# Control_HAT_v0_2A.net
KiCad netlist of a schematic drawn in EAGLE
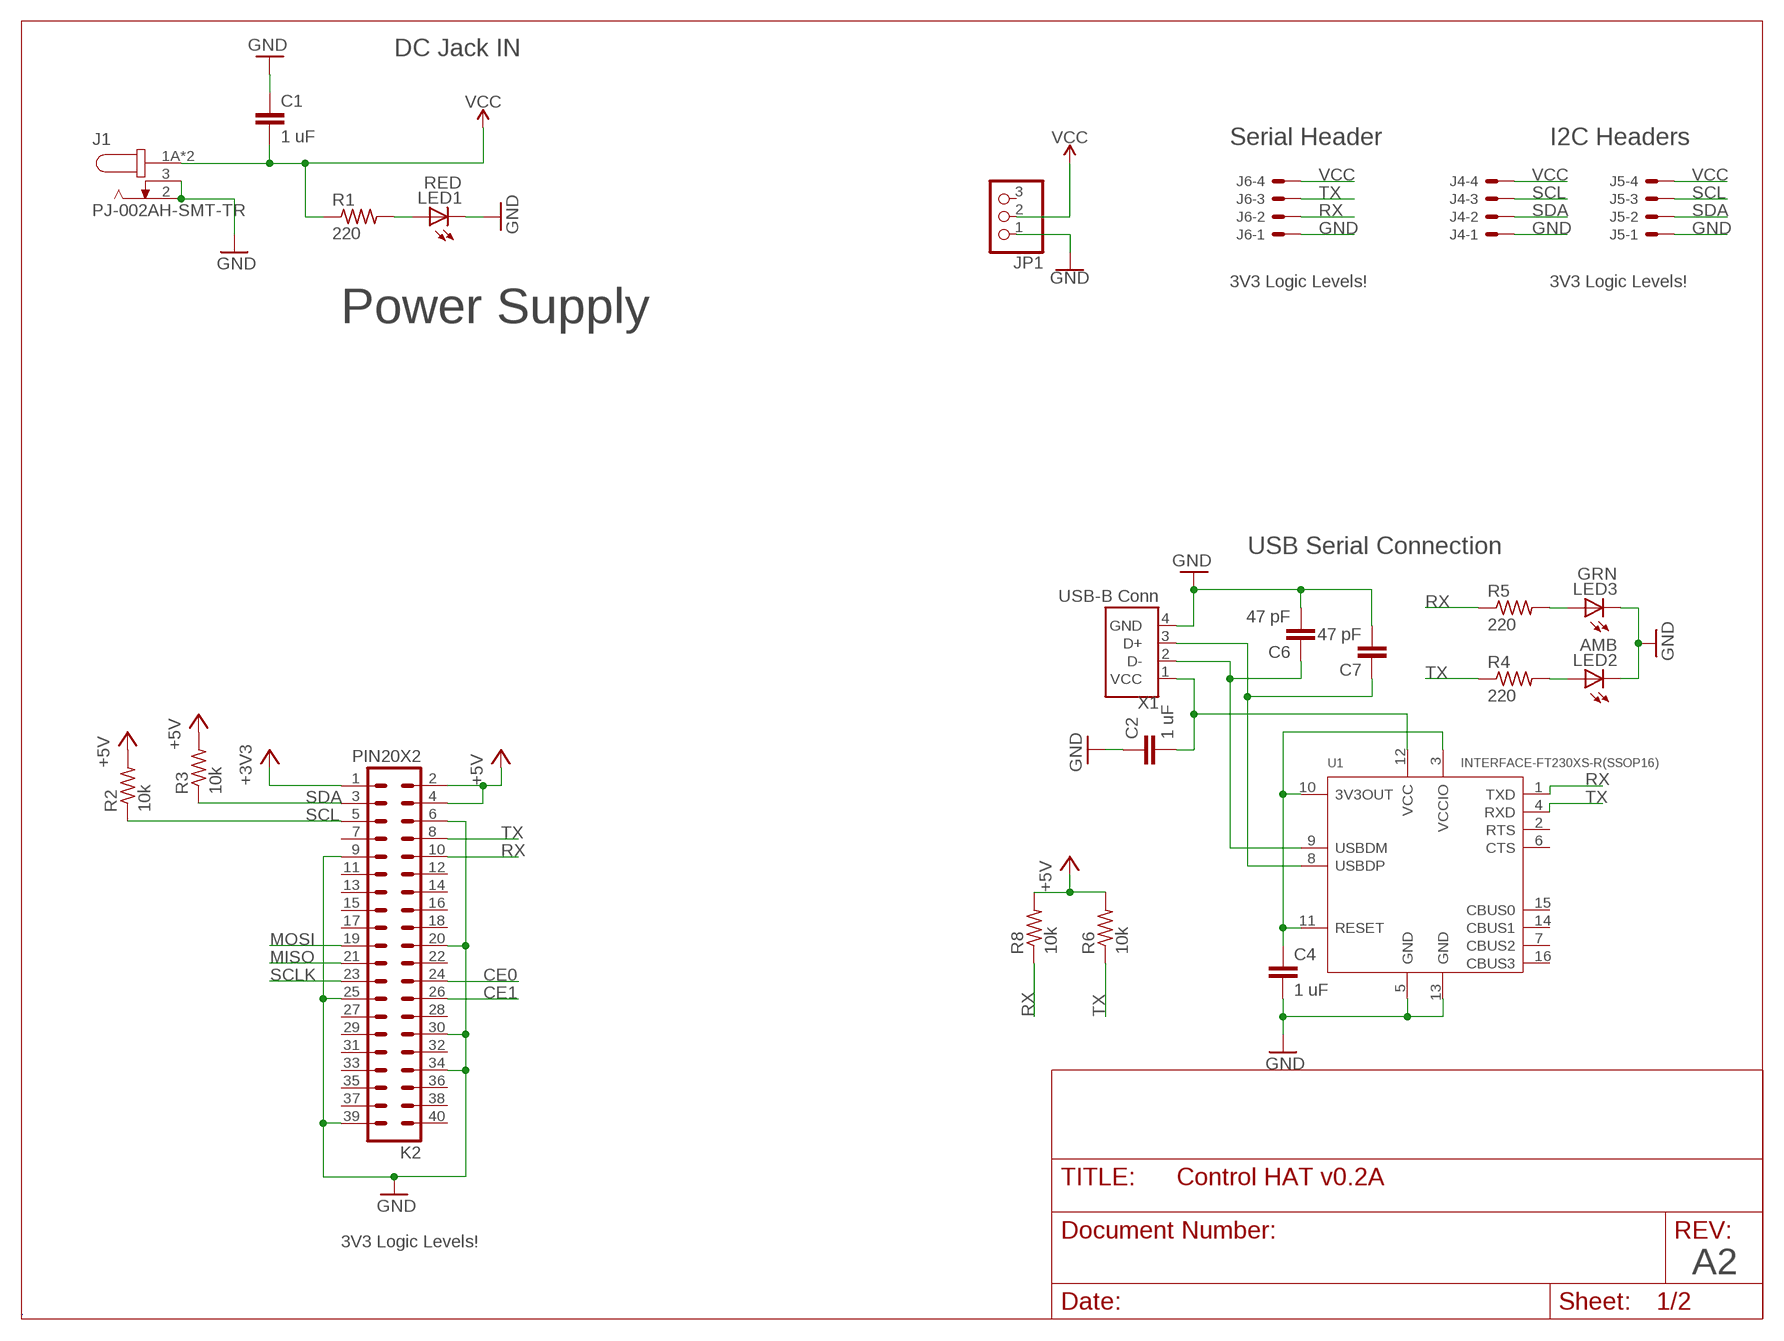
[diagram p0: schematic, sheet 1]
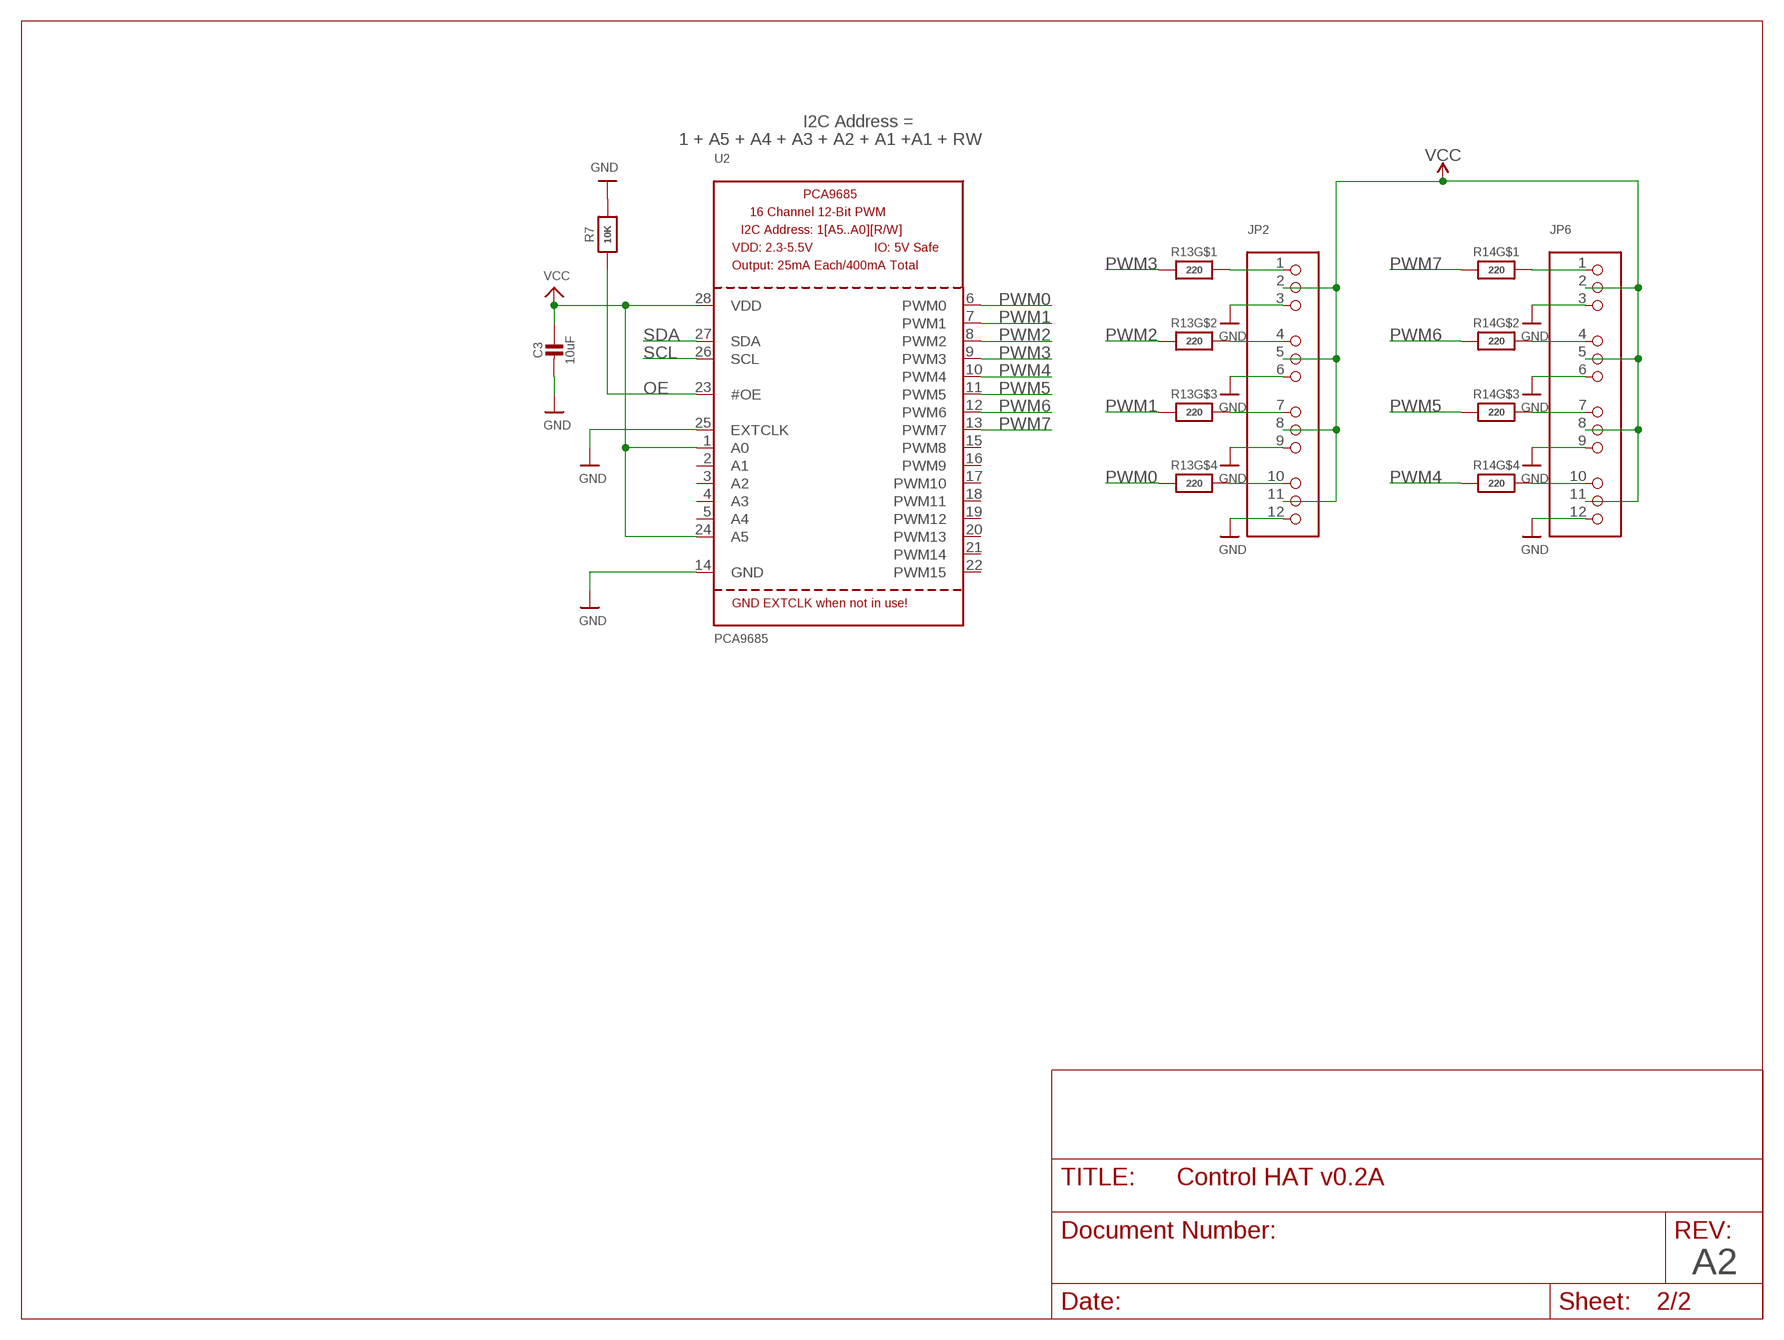
[diagram p1: schematic, sheet 2]

(export (version "E")
  (design (tool "Eeschema 10.0.6"))
  (components
    (comp (ref "C1")
      (value "1 uF")
      (footprint "eagle-import:C0603")
      (libsource (lib "eagle-import") (part "C-EUC0603"))
    )
    (comp (ref "C2")
      (value "1 uF")
      (footprint "eagle-import:C0603")
      (libsource (lib "eagle-import") (part "C-EUC0603"))
    )
    (comp (ref "C4")
      (value "1 uF")
      (footprint "eagle-import:C0603")
      (libsource (lib "eagle-import") (part "C-EUC0603"))
    )
    (comp (ref "C6")
      (value "47 pF")
      (footprint "eagle-import:C0603")
      (libsource (lib "eagle-import") (part "C-EUC0603"))
    )
    (comp (ref "C7")
      (value "47 pF")
      (footprint "eagle-import:C0603")
      (libsource (lib "eagle-import") (part "C-EUC0603"))
    )
    (comp (ref "J1")
      (value "PJ-002AH-SMT-TR")
      (footprint "eagle-import:CUI_PJ-002AH-SMT-TR")
      (fields (field (name "DIGI-KEY_PART_NUMBER") "CP-002AHPJCT-ND") (field (name "MF") "CUI Inc."))
      (libsource (lib "eagle-import") (part "PJ-002AH-SMT-TR"))
    )
    (comp (ref "J4")
      (value "JST-XH-04-PIN-LONG-PAD")
      (footprint "eagle-import:JST-XH-04-PACKAGE-LONG-PAD")
      (libsource (lib "eagle-import") (part "JST-XH-04-PIN-LONG-PAD"))
    )
    (comp (ref "J5")
      (value "JST-XH-04-PIN-LONG-PAD")
      (footprint "eagle-import:JST-XH-04-PACKAGE-LONG-PAD")
      (libsource (lib "eagle-import") (part "JST-XH-04-PIN-LONG-PAD"))
    )
    (comp (ref "J6")
      (value "JST-XH-04-PIN-LONG-PAD")
      (footprint "eagle-import:JST-XH-04-PACKAGE-LONG-PAD")
      (libsource (lib "eagle-import") (part "JST-XH-04-PIN-LONG-PAD"))
    )
    (comp (ref "JP1")
      (value "PINHD-1X3")
      (footprint "eagle-import:1X03")
      (libsource (lib "eagle-import") (part "PINHD-1X3"))
    )
    (comp (ref "K2")
      (value "PIN20X2")
      (footprint "eagle-import:PIN_20X2")
      (libsource (lib "eagle-import") (part "PIN20X2"))
    )
    (comp (ref "LED1")
      (value "RED")
      (footprint "eagle-import:CHIP-LED0603")
      (libsource (lib "eagle-import") (part "LEDCHIP-LED0603"))
    )
    (comp (ref "LED2")
      (value "AMB")
      (footprint "eagle-import:CHIP-LED0603")
      (libsource (lib "eagle-import") (part "LEDCHIP-LED0603"))
    )
    (comp (ref "LED3")
      (value "GRN")
      (footprint "eagle-import:CHIP-LED0603")
      (libsource (lib "eagle-import") (part "LEDCHIP-LED0603"))
    )
    (comp (ref "R1")
      (value "220")
      (footprint "eagle-import:M1206")
      (libsource (lib "eagle-import") (part "R-US_M1206"))
    )
    (comp (ref "R2")
      (value "10k")
      (footprint "eagle-import:M1206")
      (libsource (lib "eagle-import") (part "R-US_M1206"))
    )
    (comp (ref "R3")
      (value "10k")
      (footprint "eagle-import:M1206")
      (libsource (lib "eagle-import") (part "R-US_M1206"))
    )
    (comp (ref "R4")
      (value "220")
      (footprint "eagle-import:M1206")
      (libsource (lib "eagle-import") (part "R-US_M1206"))
    )
    (comp (ref "R5")
      (value "220")
      (footprint "eagle-import:M1206")
      (libsource (lib "eagle-import") (part "R-US_M1206"))
    )
    (comp (ref "R6")
      (value "10k")
      (footprint "eagle-import:M1206")
      (libsource (lib "eagle-import") (part "R-US_M1206"))
    )
    (comp (ref "R8")
      (value "10k")
      (footprint "eagle-import:M1206")
      (libsource (lib "eagle-import") (part "R-US_M1206"))
    )
    (comp (ref "U1")
      (value "INTERFACE-FT230XS-R(SSOP16)")
      (footprint "eagle-import:SSOP16-0.635-5X4MM")
      (fields (field (name "MF") "FTDI,") (field (name "MP") "FT230XS-R"))
      (libsource (lib "eagle-import") (part "INTERFACE-FT230XS-R(SSOP16)"))
    )
    (comp (ref "X1")
      (value "USB-B Conn")
      (footprint "eagle-import:OST_USB-B1HSB6")
      (fields (field (name "MF") "On Shore") (field (name "MP") "USB-B1HSB6"))
      (libsource (lib "eagle-import") (part "USB-B1HSB6"))
    )
    (comp (ref "C3")
      (value "10uF")
      (footprint "eagle-import:0805-NO")
      (libsource (lib "eagle-import") (part "CAP_CERAMIC0805-NOOUTLINE"))
    )
    (comp (ref "JP2")
      (value "HEADER-3X04")
      (footprint "eagle-import:3X04")
      (libsource (lib "eagle-import") (part "HEADER-3X04"))
    )
    (comp (ref "JP6")
      (value "HEADER-3X04")
      (footprint "eagle-import:3X04")
      (libsource (lib "eagle-import") (part "HEADER-3X04"))
    )
    (comp (ref "R7")
      (value "10K")
      (footprint "eagle-import:0805-NO")
      (libsource (lib "eagle-import") (part "RESISTOR0805_NOOUTLINE"))
    )
    (comp (ref "R13")
      (value "220")
      (footprint "eagle-import:RESPACK_4X0603")
      (libsource (lib "eagle-import") (part "RESISTOR_4PACK"))
    )
    (comp (ref "R14")
      (value "220")
      (footprint "eagle-import:RESPACK_4X0603")
      (libsource (lib "eagle-import") (part "RESISTOR_4PACK"))
    )
    (comp (ref "U2")
      (value "PCA9685")
      (footprint "eagle-import:TSSOP28")
      (libsource (lib "eagle-import") (part "PCA9685"))
    )
  )
  (nets
    (net (code "1") (name "+3V3") (class "Default")
      (node (ref "K2") (pin "1") (pinfunction "1_1") (pintype "passive"))
    )
    (net (code "2") (name "+5V") (class "Default")
      (node (ref "K2") (pin "2") (pinfunction "2_2") (pintype "passive"))
      (node (ref "K2") (pin "4") (pinfunction "4_4") (pintype "passive"))
      (node (ref "R2") (pin "2") (pinfunction "2_2") (pintype "passive"))
      (node (ref "R3") (pin "2") (pinfunction "2_2") (pintype "passive"))
      (node (ref "R6") (pin "2") (pinfunction "2_2") (pintype "passive"))
      (node (ref "R8") (pin "2") (pinfunction "2_2") (pintype "passive"))
    )
    (net (code "3") (name "CE0") (class "Default")
      (node (ref "K2") (pin "24") (pinfunction "24_24") (pintype "passive"))
    )
    (net (code "4") (name "CE1") (class "Default")
      (node (ref "K2") (pin "26") (pinfunction "26_26") (pintype "passive"))
    )
    (net (code "5") (name "GND") (class "Default")
      (node (ref "C1") (pin "1") (pinfunction "1_1") (pintype "passive"))
      (node (ref "C2") (pin "1") (pinfunction "1_1") (pintype "passive"))
      (node (ref "C3") (pin "2") (pinfunction "2_2") (pintype "passive"))
      (node (ref "C4") (pin "2") (pinfunction "2_2") (pintype "passive"))
      (node (ref "C6") (pin "2") (pinfunction "2_2") (pintype "passive"))
      (node (ref "C7") (pin "2") (pinfunction "2_2") (pintype "passive"))
      (node (ref "J1") (pin "2") (pinfunction "2_2") (pintype "passive"))
      (node (ref "J1") (pin "3") (pinfunction "3_3") (pintype "passive"))
      (node (ref "J4") (pin "1") (pinfunction "S_1") (pintype "passive"))
      (node (ref "J5") (pin "1") (pinfunction "S_1") (pintype "passive"))
      (node (ref "J6") (pin "1") (pinfunction "S_1") (pintype "passive"))
      (node (ref "JP1") (pin "1") (pinfunction "1_1") (pintype "passive"))
      (node (ref "JP2") (pin "12") (pinfunction "12_12") (pintype "passive"))
      (node (ref "JP2") (pin "3") (pinfunction "3_3") (pintype "passive"))
      (node (ref "JP2") (pin "6") (pinfunction "6_6") (pintype "passive"))
      (node (ref "JP2") (pin "9") (pinfunction "9_9") (pintype "passive"))
      (node (ref "JP6") (pin "12") (pinfunction "12_12") (pintype "passive"))
      (node (ref "JP6") (pin "3") (pinfunction "3_3") (pintype "passive"))
      (node (ref "JP6") (pin "6") (pinfunction "6_6") (pintype "passive"))
      (node (ref "JP6") (pin "9") (pinfunction "9_9") (pintype "passive"))
      (node (ref "K2") (pin "20") (pinfunction "20_20") (pintype "passive"))
      (node (ref "K2") (pin "25") (pinfunction "25_25") (pintype "passive"))
      (node (ref "K2") (pin "30") (pinfunction "30_30") (pintype "passive"))
      (node (ref "K2") (pin "34") (pinfunction "34_34") (pintype "passive"))
      (node (ref "K2") (pin "39") (pinfunction "39_39") (pintype "passive"))
      (node (ref "K2") (pin "6") (pinfunction "6_6") (pintype "passive"))
      (node (ref "K2") (pin "9") (pinfunction "9_9") (pintype "passive"))
      (node (ref "LED1") (pin "C") (pinfunction "C_C") (pintype "passive"))
      (node (ref "LED2") (pin "C") (pinfunction "C_C") (pintype "passive"))
      (node (ref "LED3") (pin "C") (pinfunction "C_C") (pintype "passive"))
      (node (ref "R7") (pin "2") (pinfunction "2_2") (pintype "passive"))
      (node (ref "U1") (pin "13") (pinfunction "GND_13") (pintype "bidirectional"))
      (node (ref "U1") (pin "5") (pinfunction "GND_5") (pintype "bidirectional"))
      (node (ref "U2") (pin "14") (pinfunction "GND_14") (pintype "power_in"))
      (node (ref "U2") (pin "25") (pinfunction "EXTCLK_25") (pintype "input"))
      (node (ref "X1") (pin "4") (pinfunction "GND_4") (pintype "power_in"))
    )
    (net (code "6") (name "MISO") (class "Default")
      (node (ref "K2") (pin "21") (pinfunction "21_21") (pintype "passive"))
    )
    (net (code "7") (name "MOSI") (class "Default")
      (node (ref "K2") (pin "19") (pinfunction "19_19") (pintype "passive"))
    )
    (net (code "8") (name "Net-(LED1-PadA)") (class "Default")
      (node (ref "LED1") (pin "A") (pinfunction "A_A") (pintype "passive"))
      (node (ref "R1") (pin "2") (pinfunction "2_2") (pintype "passive"))
    )
    (net (code "9") (name "Net-(LED2-PadA)") (class "Default")
      (node (ref "LED2") (pin "A") (pinfunction "A_A") (pintype "passive"))
      (node (ref "R4") (pin "2") (pinfunction "2_2") (pintype "passive"))
    )
    (net (code "10") (name "Net-(LED3-PadA)") (class "Default")
      (node (ref "LED3") (pin "A") (pinfunction "A_A") (pintype "passive"))
      (node (ref "R5") (pin "2") (pinfunction "2_2") (pintype "passive"))
    )
    (net (code "11") (name "Net-(R13A-2)") (class "Default")
      (node (ref "JP2") (pin "1") (pinfunction "1_1") (pintype "passive"))
      (node (ref "R13") (pin "8") (pinfunction "2_8") (pintype "passive"))
    )
    (net (code "12") (name "Net-(R13B-2)") (class "Default")
      (node (ref "JP2") (pin "4") (pinfunction "4_4") (pintype "passive"))
      (node (ref "R13") (pin "7") (pinfunction "2_7") (pintype "passive"))
    )
    (net (code "13") (name "Net-(R13C-2)") (class "Default")
      (node (ref "JP2") (pin "7") (pinfunction "7_7") (pintype "passive"))
      (node (ref "R13") (pin "6") (pinfunction "2_6") (pintype "passive"))
    )
    (net (code "14") (name "Net-(R13D-2)") (class "Default")
      (node (ref "JP2") (pin "10") (pinfunction "10_10") (pintype "passive"))
      (node (ref "R13") (pin "5") (pinfunction "2_5") (pintype "passive"))
    )
    (net (code "15") (name "Net-(R14A-2)") (class "Default")
      (node (ref "JP6") (pin "1") (pinfunction "1_1") (pintype "passive"))
      (node (ref "R14") (pin "8") (pinfunction "2_8") (pintype "passive"))
    )
    (net (code "16") (name "Net-(R14B-2)") (class "Default")
      (node (ref "JP6") (pin "4") (pinfunction "4_4") (pintype "passive"))
      (node (ref "R14") (pin "7") (pinfunction "2_7") (pintype "passive"))
    )
    (net (code "17") (name "Net-(R14C-2)") (class "Default")
      (node (ref "JP6") (pin "7") (pinfunction "7_7") (pintype "passive"))
      (node (ref "R14") (pin "6") (pinfunction "2_6") (pintype "passive"))
    )
    (net (code "18") (name "Net-(R14D-2)") (class "Default")
      (node (ref "JP6") (pin "10") (pinfunction "10_10") (pintype "passive"))
      (node (ref "R14") (pin "5") (pinfunction "2_5") (pintype "passive"))
    )
    (net (code "19") (name "Net-(U1-3V3OUT)") (class "Default")
      (node (ref "C4") (pin "1") (pinfunction "1_1") (pintype "passive"))
      (node (ref "U1") (pin "10") (pinfunction "3V3OUT_10") (pintype "bidirectional"))
      (node (ref "U1") (pin "11") (pinfunction "RESET_11") (pintype "bidirectional"))
      (node (ref "U1") (pin "3") (pinfunction "VCCIO_3") (pintype "bidirectional"))
    )
    (net (code "20") (name "Net-(U1-USBDM)") (class "Default")
      (node (ref "C6") (pin "1") (pinfunction "1_1") (pintype "passive"))
      (node (ref "U1") (pin "9") (pinfunction "USBDM_9") (pintype "bidirectional"))
      (node (ref "X1") (pin "2") (pinfunction "D-_2") (pintype "bidirectional"))
    )
    (net (code "21") (name "Net-(U1-USBDP)") (class "Default")
      (node (ref "C7") (pin "1") (pinfunction "1_1") (pintype "passive"))
      (node (ref "U1") (pin "8") (pinfunction "USBDP_8") (pintype "bidirectional"))
      (node (ref "X1") (pin "3") (pinfunction "D+_3") (pintype "bidirectional"))
    )
    (net (code "22") (name "Net-(U1-VCC)") (class "Default")
      (node (ref "C2") (pin "2") (pinfunction "2_2") (pintype "passive"))
      (node (ref "U1") (pin "12") (pinfunction "VCC_12") (pintype "bidirectional"))
      (node (ref "X1") (pin "1") (pinfunction "VCC_1") (pintype "power_in"))
    )
    (net (code "23") (name "OE") (class "Default")
      (node (ref "R7") (pin "1") (pinfunction "1_1") (pintype "passive"))
      (node (ref "U2") (pin "23") (pinfunction "#OE_23") (pintype "input"))
    )
    (net (code "24") (name "PWM0") (class "Default")
      (node (ref "R13") (pin "4") (pinfunction "1_4") (pintype "passive"))
      (node (ref "U2") (pin "6") (pinfunction "PWM0_6") (pintype "output"))
    )
    (net (code "25") (name "PWM1") (class "Default")
      (node (ref "R13") (pin "3") (pinfunction "1_3") (pintype "passive"))
      (node (ref "U2") (pin "7") (pinfunction "PWM1_7") (pintype "output"))
    )
    (net (code "26") (name "PWM2") (class "Default")
      (node (ref "R13") (pin "2") (pinfunction "1_2") (pintype "passive"))
      (node (ref "U2") (pin "8") (pinfunction "PWM2_8") (pintype "output"))
    )
    (net (code "27") (name "PWM3") (class "Default")
      (node (ref "R13") (pin "1") (pinfunction "1_1") (pintype "passive"))
      (node (ref "U2") (pin "9") (pinfunction "PWM3_9") (pintype "output"))
    )
    (net (code "28") (name "PWM4") (class "Default")
      (node (ref "R14") (pin "4") (pinfunction "1_4") (pintype "passive"))
      (node (ref "U2") (pin "10") (pinfunction "PWM4_10") (pintype "output"))
    )
    (net (code "29") (name "PWM5") (class "Default")
      (node (ref "R14") (pin "3") (pinfunction "1_3") (pintype "passive"))
      (node (ref "U2") (pin "11") (pinfunction "PWM5_11") (pintype "output"))
    )
    (net (code "30") (name "PWM6") (class "Default")
      (node (ref "R14") (pin "2") (pinfunction "1_2") (pintype "passive"))
      (node (ref "U2") (pin "12") (pinfunction "PWM6_12") (pintype "output"))
    )
    (net (code "31") (name "PWM7") (class "Default")
      (node (ref "R14") (pin "1") (pinfunction "1_1") (pintype "passive"))
      (node (ref "U2") (pin "13") (pinfunction "PWM7_13") (pintype "output"))
    )
    (net (code "32") (name "RX") (class "Default")
      (node (ref "J6") (pin "2") (pinfunction "S_2") (pintype "passive"))
      (node (ref "K2") (pin "10") (pinfunction "10_10") (pintype "passive"))
      (node (ref "R5") (pin "1") (pinfunction "1_1") (pintype "passive"))
      (node (ref "R8") (pin "1") (pinfunction "1_1") (pintype "passive"))
      (node (ref "U1") (pin "1") (pinfunction "TXD_1") (pintype "bidirectional"))
    )
    (net (code "33") (name "SCL") (class "Default")
      (node (ref "J4") (pin "3") (pinfunction "S_3") (pintype "passive"))
      (node (ref "J5") (pin "3") (pinfunction "S_3") (pintype "passive"))
      (node (ref "K2") (pin "5") (pinfunction "5_5") (pintype "passive"))
      (node (ref "R2") (pin "1") (pinfunction "1_1") (pintype "passive"))
      (node (ref "U2") (pin "26") (pinfunction "SCL_26") (pintype "bidirectional"))
    )
    (net (code "34") (name "SCLK") (class "Default")
      (node (ref "K2") (pin "23") (pinfunction "23_23") (pintype "passive"))
    )
    (net (code "35") (name "SDA") (class "Default")
      (node (ref "J4") (pin "2") (pinfunction "S_2") (pintype "passive"))
      (node (ref "J5") (pin "2") (pinfunction "S_2") (pintype "passive"))
      (node (ref "K2") (pin "3") (pinfunction "3_3") (pintype "passive"))
      (node (ref "R3") (pin "1") (pinfunction "1_1") (pintype "passive"))
      (node (ref "U2") (pin "27") (pinfunction "SDA_27") (pintype "bidirectional"))
    )
    (net (code "36") (name "TX") (class "Default")
      (node (ref "J6") (pin "3") (pinfunction "S_3") (pintype "passive"))
      (node (ref "K2") (pin "8") (pinfunction "8_8") (pintype "passive"))
      (node (ref "R4") (pin "1") (pinfunction "1_1") (pintype "passive"))
      (node (ref "R6") (pin "1") (pinfunction "1_1") (pintype "passive"))
      (node (ref "U1") (pin "4") (pinfunction "RXD_4") (pintype "bidirectional"))
    )
    (net (code "37") (name "VCC") (class "Default")
      (node (ref "C1") (pin "2") (pinfunction "2_2") (pintype "passive"))
      (node (ref "C3") (pin "1") (pinfunction "1_1") (pintype "passive"))
      (node (ref "J1") (pin "1A") (pinfunction "1_1A") (pintype "passive"))
      (node (ref "J1") (pin "1B") (pinfunction "1_1B") (pintype "passive"))
      (node (ref "J4") (pin "4") (pinfunction "S_4") (pintype "passive"))
      (node (ref "J5") (pin "4") (pinfunction "S_4") (pintype "passive"))
      (node (ref "J6") (pin "4") (pinfunction "S_4") (pintype "passive"))
      (node (ref "JP1") (pin "2") (pinfunction "2_2") (pintype "passive"))
      (node (ref "JP2") (pin "11") (pinfunction "11_11") (pintype "passive"))
      (node (ref "JP2") (pin "2") (pinfunction "2_2") (pintype "passive"))
      (node (ref "JP2") (pin "5") (pinfunction "5_5") (pintype "passive"))
      (node (ref "JP2") (pin "8") (pinfunction "8_8") (pintype "passive"))
      (node (ref "JP6") (pin "11") (pinfunction "11_11") (pintype "passive"))
      (node (ref "JP6") (pin "2") (pinfunction "2_2") (pintype "passive"))
      (node (ref "JP6") (pin "5") (pinfunction "5_5") (pintype "passive"))
      (node (ref "JP6") (pin "8") (pinfunction "8_8") (pintype "passive"))
      (node (ref "R1") (pin "1") (pinfunction "1_1") (pintype "passive"))
      (node (ref "U2") (pin "1") (pinfunction "A0_1") (pintype "bidirectional"))
      (node (ref "U2") (pin "24") (pinfunction "A5_24") (pintype "bidirectional"))
      (node (ref "U2") (pin "28") (pinfunction "VDD_28") (pintype "power_in"))
    )
    (net (code "38") (name "unconnected-(JP1-Pad3)") (class "Default")
      (node (ref "JP1") (pin "3") (pinfunction "3_3") (pintype "passive"))
    )
    (net (code "39") (name "unconnected-(K2-Pad7)") (class "Default")
      (node (ref "K2") (pin "7") (pinfunction "7_7") (pintype "passive"))
    )
    (net (code "40") (name "unconnected-(K2-Pad11)") (class "Default")
      (node (ref "K2") (pin "11") (pinfunction "11_11") (pintype "passive"))
    )
    (net (code "41") (name "unconnected-(K2-Pad12)") (class "Default")
      (node (ref "K2") (pin "12") (pinfunction "12_12") (pintype "passive"))
    )
    (net (code "42") (name "unconnected-(K2-Pad13)") (class "Default")
      (node (ref "K2") (pin "13") (pinfunction "13_13") (pintype "passive"))
    )
    (net (code "43") (name "unconnected-(K2-Pad14)") (class "Default")
      (node (ref "K2") (pin "14") (pinfunction "14_14") (pintype "passive"))
    )
    (net (code "44") (name "unconnected-(K2-Pad15)") (class "Default")
      (node (ref "K2") (pin "15") (pinfunction "15_15") (pintype "passive"))
    )
    (net (code "45") (name "unconnected-(K2-Pad16)") (class "Default")
      (node (ref "K2") (pin "16") (pinfunction "16_16") (pintype "passive"))
    )
    (net (code "46") (name "unconnected-(K2-Pad17)") (class "Default")
      (node (ref "K2") (pin "17") (pinfunction "17_17") (pintype "passive"))
    )
    (net (code "47") (name "unconnected-(K2-Pad18)") (class "Default")
      (node (ref "K2") (pin "18") (pinfunction "18_18") (pintype "passive"))
    )
    (net (code "48") (name "unconnected-(K2-Pad22)") (class "Default")
      (node (ref "K2") (pin "22") (pinfunction "22_22") (pintype "passive"))
    )
    (net (code "49") (name "unconnected-(K2-Pad27)") (class "Default")
      (node (ref "K2") (pin "27") (pinfunction "27_27") (pintype "passive"))
    )
    (net (code "50") (name "unconnected-(K2-Pad28)") (class "Default")
      (node (ref "K2") (pin "28") (pinfunction "28_28") (pintype "passive"))
    )
    (net (code "51") (name "unconnected-(K2-Pad29)") (class "Default")
      (node (ref "K2") (pin "29") (pinfunction "29_29") (pintype "passive"))
    )
    (net (code "52") (name "unconnected-(K2-Pad31)") (class "Default")
      (node (ref "K2") (pin "31") (pinfunction "31_31") (pintype "passive"))
    )
    (net (code "53") (name "unconnected-(K2-Pad32)") (class "Default")
      (node (ref "K2") (pin "32") (pinfunction "32_32") (pintype "passive"))
    )
    (net (code "54") (name "unconnected-(K2-Pad33)") (class "Default")
      (node (ref "K2") (pin "33") (pinfunction "33_33") (pintype "passive"))
    )
    (net (code "55") (name "unconnected-(K2-Pad35)") (class "Default")
      (node (ref "K2") (pin "35") (pinfunction "35_35") (pintype "passive"))
    )
    (net (code "56") (name "unconnected-(K2-Pad36)") (class "Default")
      (node (ref "K2") (pin "36") (pinfunction "36_36") (pintype "passive"))
    )
    (net (code "57") (name "unconnected-(K2-Pad37)") (class "Default")
      (node (ref "K2") (pin "37") (pinfunction "37_37") (pintype "passive"))
    )
    (net (code "58") (name "unconnected-(K2-Pad38)") (class "Default")
      (node (ref "K2") (pin "38") (pinfunction "38_38") (pintype "passive"))
    )
    (net (code "59") (name "unconnected-(K2-Pad40)") (class "Default")
      (node (ref "K2") (pin "40") (pinfunction "40_40") (pintype "passive"))
    )
    (net (code "60") (name "unconnected-(U1-CBUS0-Pad15)") (class "Default")
      (node (ref "U1") (pin "15") (pinfunction "CBUS0_15") (pintype "bidirectional"))
    )
    (net (code "61") (name "unconnected-(U1-CBUS1-Pad14)") (class "Default")
      (node (ref "U1") (pin "14") (pinfunction "CBUS1_14") (pintype "bidirectional"))
    )
    (net (code "62") (name "unconnected-(U1-CBUS2-Pad7)") (class "Default")
      (node (ref "U1") (pin "7") (pinfunction "CBUS2_7") (pintype "bidirectional"))
    )
    (net (code "63") (name "unconnected-(U1-CBUS3-Pad16)") (class "Default")
      (node (ref "U1") (pin "16") (pinfunction "CBUS3_16") (pintype "bidirectional"))
    )
    (net (code "64") (name "unconnected-(U1-CTS-Pad6)") (class "Default")
      (node (ref "U1") (pin "6") (pinfunction "CTS_6") (pintype "bidirectional"))
    )
    (net (code "65") (name "unconnected-(U1-RTS-Pad2)") (class "Default")
      (node (ref "U1") (pin "2") (pinfunction "RTS_2") (pintype "bidirectional"))
    )
    (net (code "66") (name "unconnected-(U2-A1-Pad2)") (class "Default")
      (node (ref "U2") (pin "2") (pinfunction "A1_2") (pintype "bidirectional"))
    )
    (net (code "67") (name "unconnected-(U2-A2-Pad3)") (class "Default")
      (node (ref "U2") (pin "3") (pinfunction "A2_3") (pintype "bidirectional"))
    )
    (net (code "68") (name "unconnected-(U2-A3-Pad4)") (class "Default")
      (node (ref "U2") (pin "4") (pinfunction "A3_4") (pintype "bidirectional"))
    )
    (net (code "69") (name "unconnected-(U2-A4-Pad5)") (class "Default")
      (node (ref "U2") (pin "5") (pinfunction "A4_5") (pintype "bidirectional"))
    )
    (net (code "70") (name "unconnected-(U2-PWM8-Pad15)") (class "Default")
      (node (ref "U2") (pin "15") (pinfunction "PWM8_15") (pintype "output"))
    )
    (net (code "71") (name "unconnected-(U2-PWM9-Pad16)") (class "Default")
      (node (ref "U2") (pin "16") (pinfunction "PWM9_16") (pintype "output"))
    )
    (net (code "72") (name "unconnected-(U2-PWM10-Pad17)") (class "Default")
      (node (ref "U2") (pin "17") (pinfunction "PWM10_17") (pintype "output"))
    )
    (net (code "73") (name "unconnected-(U2-PWM11-Pad18)") (class "Default")
      (node (ref "U2") (pin "18") (pinfunction "PWM11_18") (pintype "output"))
    )
    (net (code "74") (name "unconnected-(U2-PWM12-Pad19)") (class "Default")
      (node (ref "U2") (pin "19") (pinfunction "PWM12_19") (pintype "output"))
    )
    (net (code "75") (name "unconnected-(U2-PWM13-Pad20)") (class "Default")
      (node (ref "U2") (pin "20") (pinfunction "PWM13_20") (pintype "output"))
    )
    (net (code "76") (name "unconnected-(U2-PWM14-Pad21)") (class "Default")
      (node (ref "U2") (pin "21") (pinfunction "PWM14_21") (pintype "output"))
    )
    (net (code "77") (name "unconnected-(U2-PWM15-Pad22)") (class "Default")
      (node (ref "U2") (pin "22") (pinfunction "PWM15_22") (pintype "output"))
    )
  )
)
